# Power_Supply.net
KiCad netlist of a schematic drawn in Altium Designer
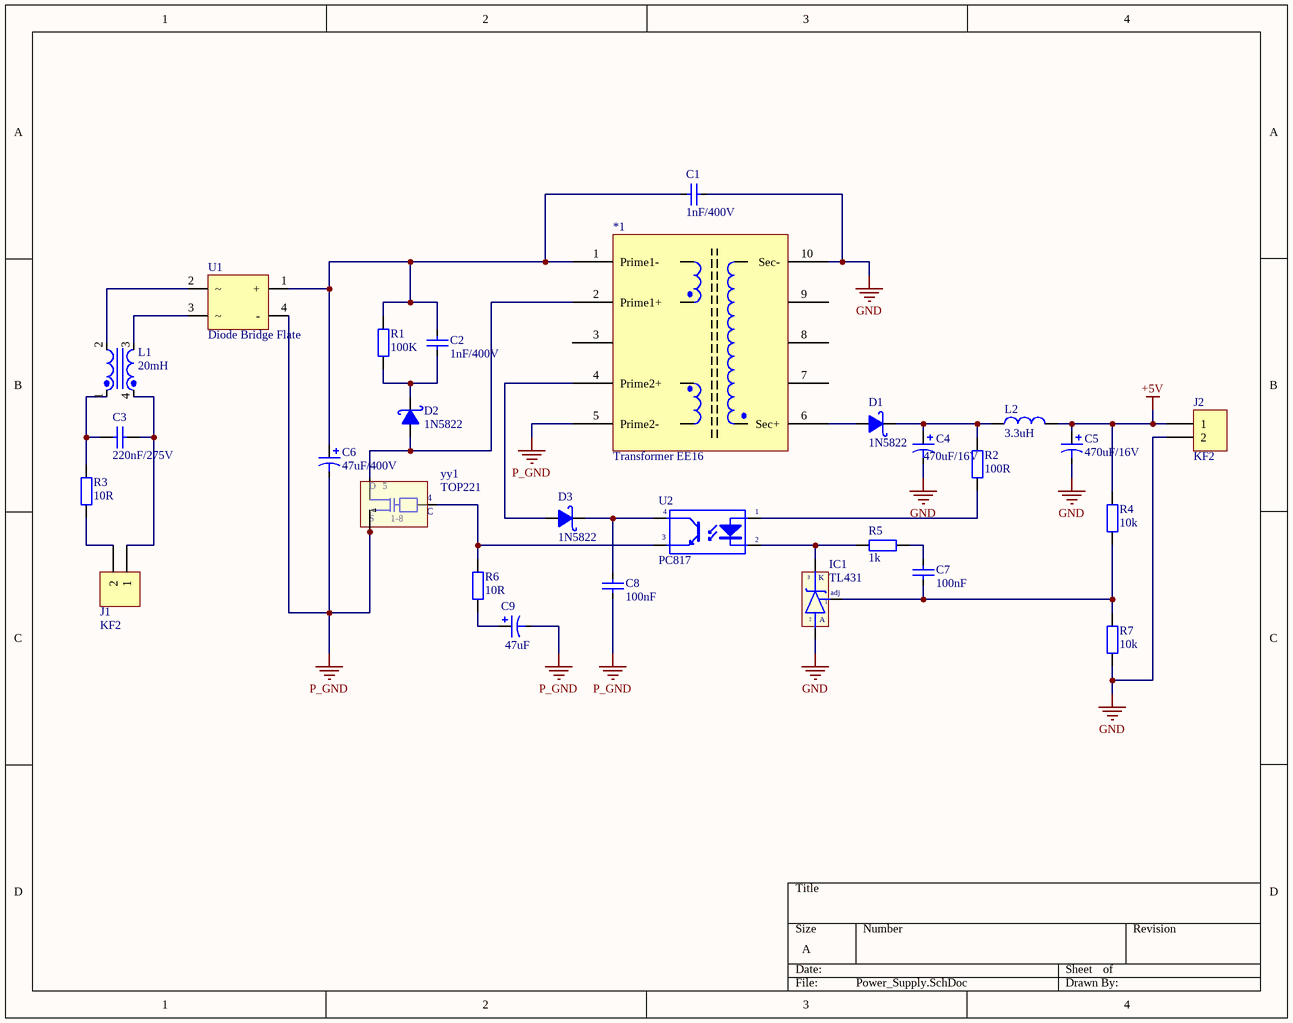
[diagram p0: Power_Supply.SchDoc]

(export (version "E")
  (design (tool "Eeschema 10.0.6"))
  (components
    (comp (ref "*1")
      (value "Transformer EE16")
      (footprint "Transformer SW")
      (libsource (lib "My Library") (part "Transformer EE16"))
    )
    (comp (ref "C1")
      (value "1nF/400V")
      (footprint "103/2KV")
      (description "Capacitor Ceramic 2KV")
      (fields (field (name "PUBLISHER") "Altium Limited"))
      (libsource (lib "My Library") (part "Cap2KV"))
    )
    (comp (ref "C2")
      (value "1nF/400V")
      (footprint "103/2KV")
      (description "Capacitor Ceramic 2KV")
      (fields (field (name "PUBLISHER") "Altium Limited"))
      (libsource (lib "My Library") (part "Cap2KV"))
    )
    (comp (ref "C3")
      (value "220nF/275V")
      (footprint "CN3")
      (description "Capacitor")
      (fields (field (name "Comment") "Capacitor Ceramic") (field (name "PUBLISHER") "Altium Limited"))
      (libsource (lib "My Library") (part "CapCeramic"))
    )
    (comp (ref "C4")
      (value "470uF/16V")
      (footprint "C5mm")
      (description "Polarized Capacitor (Axial)")
      (fields (field (name "PUBLISHER") "Altium Limited"))
      (libsource (lib "My Library") (part "Cap Pol"))
    )
    (comp (ref "C5")
      (value "470uF/16V")
      (footprint "C5mm")
      (description "Polarized Capacitor (Axial)")
      (fields (field (name "PUBLISHER") "Altium Limited"))
      (libsource (lib "My Library") (part "Cap Pol"))
    )
    (comp (ref "C6")
      (value "47uF/400V")
      (footprint "C10mm")
      (description "Polarized Capacitor (Axial)")
      (fields (field (name "PUBLISHER") "Altium Limited"))
      (libsource (lib "My Library") (part "Cap Pol"))
    )
    (comp (ref "C7")
      (value "100nF")
      (footprint "103/2KV")
      (description "Capacitor Ceramic 2KV")
      (fields (field (name "PUBLISHER") "Altium Limited"))
      (libsource (lib "My Library") (part "Cap2KV"))
    )
    (comp (ref "C8")
      (value "100nF")
      (footprint "103/2KV")
      (description "Capacitor Ceramic 2KV")
      (fields (field (name "PUBLISHER") "Altium Limited"))
      (libsource (lib "My Library") (part "Cap2KV"))
    )
    (comp (ref "C9")
      (value "47uF")
      (footprint "C3MM")
      (description "Polarized Capacitor (Axial)")
      (fields (field (name "PUBLISHER") "Altium Limited"))
      (libsource (lib "My Library") (part "Cap Pol"))
    )
    (comp (ref "D1")
      (value "1N5822")
      (footprint "DO-214AC(SMA)")
      (description "Schottky Rectifiers")
      (libsource (lib "My Library") (part "1N5822"))
    )
    (comp (ref "D2")
      (value "1N5822")
      (footprint "DO-214AC(SMA)")
      (description "Schottky Rectifiers")
      (libsource (lib "My Library") (part "1N5822"))
    )
    (comp (ref "D3")
      (value "1N5822")
      (footprint "DO-214AC(SMA)")
      (description "Schottky Rectifiers")
      (libsource (lib "My Library") (part "1N5822"))
    )
    (comp (ref "IC1")
      (value "TL431")
      (footprint "qto-92")
      (description "Programmable Shunt Regulator")
      (libsource (lib "My Library") (part "TL431"))
    )
    (comp (ref "J1")
      (value "KF2")
      (footprint "KF2-5.08")
      (fields
        (field (name "MANUFACTURER") "Würth Elektronik eiSos GmbH")
        (field (name "PARTNO") "691103110002")
        (field (name "CREATED BY") "Karrer Zheng")
      )
      (libsource (lib "") (part "KF2_1"))
    )
    (comp (ref "J2")
      (value "KF2")
      (footprint "KF2-5.08")
      (fields
        (field (name "MANUFACTURER") "Würth Elektronik eiSos GmbH")
        (field (name "PARTNO") "691103110002")
        (field (name "CREATED BY") "Karrer Zheng")
      )
      (libsource (lib "My Library") (part "KF2"))
    )
    (comp (ref "L1")
      (value "20mH")
      (footprint "InductorFilter")
      (description "Inductor")
      (fields (field (name "DESIGNED BY") "VanDungEvn"))
      (libsource (lib "My Library") (part "L fiter"))
    )
    (comp (ref "L2")
      (value "3.3uH")
      (footprint "My Library:L-SMD-M-12x10")
      (description "Inductor")
      (libsource (lib "My Library") (part "Inductor"))
    )
    (comp (ref "R1")
      (value "100K")
      (footprint "RES-1WD")
      (description "Resistor SMD")
      (libsource (lib "My Library") (part "RM"))
    )
    (comp (ref "R2")
      (value "100R")
      (footprint "SM-0805")
      (description "Resistor SMD")
      (libsource (lib "My Library") (part "RM"))
    )
    (comp (ref "R3")
      (value "10R")
      (footprint "RES-1WD")
      (description "Resistor SMD")
      (libsource (lib "My Library") (part "RM"))
    )
    (comp (ref "R4")
      (value "10k")
      (footprint "SM-0805")
      (description "Resistor SMD")
      (libsource (lib "My Library") (part "RM"))
    )
    (comp (ref "R5")
      (value "1k")
      (footprint "SM-0805")
      (description "Resistor SMD")
      (libsource (lib "My Library") (part "RM"))
    )
    (comp (ref "R6")
      (value "10R")
      (footprint "SM-0805")
      (description "Resistor SMD")
      (libsource (lib "My Library") (part "RM"))
    )
    (comp (ref "R7")
      (value "10k")
      (footprint "SM-0805")
      (description "Resistor SMD")
      (libsource (lib "My Library") (part "RM"))
    )
    (comp (ref "U1")
      (value "Diode Bridge Flate")
      (footprint "CAU 1A")
      (description "Diode Bridge")
      (libsource (lib "My Library") (part "Diode Bridge Flate"))
    )
    (comp (ref "U2")
      (value "PC817")
      (footprint "DIP4/W0.3")
      (description "Single Opto")
      (libsource (lib "My Library") (part "PC817"))
    )
    (comp (ref "yy1")
      (value "TOP221")
      (footprint "DIP8/W0.3")
      (description "Family Three-terminal Off-line PWM Switch")
      (libsource (lib "My Library") (part "TOP221-7PG"))
    )
  )
  (nets
    (net (code "1") (name "+5V") (class "Default")
      (node (ref "C5") (pin "1") (pinfunction "1_1") (pintype "passive"))
      (node (ref "J2") (pin "1") (pinfunction "1_1") (pintype "passive"))
      (node (ref "L2") (pin "2") (pinfunction "2_2") (pintype "passive"))
      (node (ref "R4") (pin "1") (pinfunction "1_1") (pintype "passive"))
    )
    (net (code "2") (name "GND") (class "Default")
      (node (ref "*1") (pin "10") (pinfunction "Sec-_10") (pintype "passive"))
      (node (ref "C1") (pin "1") (pinfunction "1_1") (pintype "passive"))
      (node (ref "C4") (pin "2") (pinfunction "2_2") (pintype "passive"))
      (node (ref "C5") (pin "2") (pinfunction "2_2") (pintype "passive"))
      (node (ref "IC1") (pin "2") (pinfunction "A_2") (pintype "passive"))
      (node (ref "J2") (pin "2") (pinfunction "2_2") (pintype "passive"))
      (node (ref "R7") (pin "2") (pinfunction "2_2") (pintype "passive"))
    )
    (net (code "3") (name "Net-(*1-Prime1+)") (class "Default")
      (node (ref "*1") (pin "2") (pinfunction "Prime1+_2") (pintype "passive"))
      (node (ref "D2") (pin "1") (pinfunction "A_1") (pintype "passive"))
      (node (ref "yy1") (pin "5") (pinfunction "D_5") (pintype "passive"))
    )
    (net (code "4") (name "Net-(*1-Prime1-)") (class "Default")
      (node (ref "*1") (pin "1") (pinfunction "Prime1-_1") (pintype "passive"))
      (node (ref "C1") (pin "2") (pinfunction "2_2") (pintype "passive"))
      (node (ref "C2") (pin "2") (pinfunction "2_2") (pintype "passive"))
      (node (ref "C6") (pin "1") (pinfunction "1_1") (pintype "passive"))
      (node (ref "R1") (pin "2") (pinfunction "2_2") (pintype "passive"))
      (node (ref "U1") (pin "1") (pinfunction "+_1") (pintype "passive"))
    )
    (net (code "5") (name "Net-(*1-Prime2+)") (class "Default")
      (node (ref "*1") (pin "4") (pinfunction "Prime2+_4") (pintype "passive"))
      (node (ref "D3") (pin "1") (pinfunction "A_1") (pintype "passive"))
    )
    (net (code "6") (name "Net-(*1-Sec+)") (class "Default")
      (node (ref "*1") (pin "6") (pinfunction "Sec+_6") (pintype "passive"))
      (node (ref "D1") (pin "1") (pinfunction "A_1") (pintype "passive"))
    )
    (net (code "7") (name "Net-(C3-Pad1)") (class "Default")
      (node (ref "C3") (pin "1") (pinfunction "1_1") (pintype "passive"))
      (node (ref "L1") (pin "1") (pintype "passive"))
      (node (ref "R3") (pin "2") (pinfunction "2_2") (pintype "passive"))
    )
    (net (code "8") (name "Net-(C3-Pad2)") (class "Default")
      (node (ref "C3") (pin "2") (pinfunction "2_2") (pintype "passive"))
      (node (ref "J1") (pin "1") (pinfunction "1_1") (pintype "passive"))
      (node (ref "L1") (pin "4") (pintype "passive"))
    )
    (net (code "9") (name "Net-(C7-Pad2)") (class "Default")
      (node (ref "C7") (pin "2") (pinfunction "2_2") (pintype "passive"))
      (node (ref "R5") (pin "1") (pinfunction "1_1") (pintype "passive"))
    )
    (net (code "10") (name "Net-(C9-Pad1)") (class "Default")
      (node (ref "C9") (pin "1") (pinfunction "1_1") (pintype "passive"))
      (node (ref "R6") (pin "1") (pinfunction "1_1") (pintype "passive"))
    )
    (net (code "11") (name "Net-(D1-K)") (class "Default")
      (node (ref "C4") (pin "1") (pinfunction "1_1") (pintype "passive"))
      (node (ref "D1") (pin "2") (pinfunction "K_2") (pintype "passive"))
      (node (ref "L2") (pin "1") (pinfunction "1_1") (pintype "passive"))
      (node (ref "R2") (pin "2") (pinfunction "2_2") (pintype "passive"))
    )
    (net (code "12") (name "Net-(D2-K)") (class "Default")
      (node (ref "C2") (pin "1") (pinfunction "1_1") (pintype "passive"))
      (node (ref "D2") (pin "2") (pinfunction "K_2") (pintype "passive"))
      (node (ref "R1") (pin "1") (pinfunction "1_1") (pintype "passive"))
    )
    (net (code "13") (name "Net-(D3-K)") (class "Default")
      (node (ref "C8") (pin "2") (pinfunction "2_2") (pintype "passive"))
      (node (ref "D3") (pin "2") (pinfunction "K_2") (pintype "passive"))
      (node (ref "U2") (pin "4") (pinfunction "C_4") (pintype "passive"))
    )
    (net (code "14") (name "Net-(IC1-K)") (class "Default")
      (node (ref "IC1") (pin "3") (pinfunction "K_3") (pintype "passive"))
      (node (ref "R5") (pin "2") (pinfunction "2_2") (pintype "passive"))
      (node (ref "U2") (pin "2") (pinfunction "K_2") (pintype "passive"))
    )
    (net (code "15") (name "Net-(IC1-adj)") (class "Default")
      (node (ref "C7") (pin "1") (pinfunction "1_1") (pintype "passive"))
      (node (ref "IC1") (pin "1") (pinfunction "adj_1") (pintype "passive"))
      (node (ref "R4") (pin "2") (pinfunction "2_2") (pintype "passive"))
      (node (ref "R7") (pin "1") (pinfunction "1_1") (pintype "passive"))
    )
    (net (code "16") (name "Net-(J1-Pad2)") (class "Default")
      (node (ref "J1") (pin "2") (pinfunction "2_2") (pintype "passive"))
      (node (ref "R3") (pin "1") (pinfunction "1_1") (pintype "passive"))
    )
    (net (code "17") (name "Net-(L1-Pad2)") (class "Default")
      (node (ref "L1") (pin "2") (pintype "passive"))
      (node (ref "U1") (pin "2") (pinfunction "~_2") (pintype "passive"))
    )
    (net (code "18") (name "Net-(L1-Pad3)") (class "Default")
      (node (ref "L1") (pin "3") (pintype "passive"))
      (node (ref "U1") (pin "3") (pinfunction "~_3") (pintype "passive"))
    )
    (net (code "19") (name "Net-(U2-A)") (class "Default")
      (node (ref "R2") (pin "1") (pinfunction "1_1") (pintype "passive"))
      (node (ref "U2") (pin "1") (pinfunction "A_1") (pintype "passive"))
    )
    (net (code "20") (name "Net-(U2-E)") (class "Default")
      (node (ref "R6") (pin "2") (pinfunction "2_2") (pintype "passive"))
      (node (ref "U2") (pin "3") (pinfunction "E_3") (pintype "passive"))
      (node (ref "yy1") (pin "4") (pinfunction "C_4") (pintype "passive"))
    )
    (net (code "21") (name "P_GND") (class "Default")
      (node (ref "*1") (pin "5") (pinfunction "Prime2-_5") (pintype "passive"))
      (node (ref "C6") (pin "2") (pinfunction "2_2") (pintype "passive"))
      (node (ref "C8") (pin "1") (pinfunction "1_1") (pintype "passive"))
      (node (ref "C9") (pin "2") (pinfunction "2_2") (pintype "passive"))
      (node (ref "U1") (pin "4") (pinfunction "-_4") (pintype "passive"))
      (node (ref "yy1") (pin "1") (pinfunction "S_1") (pintype "passive"))
      (node (ref "yy1") (pin "2") (pinfunction "S_2") (pintype "passive"))
      (node (ref "yy1") (pin "3") (pinfunction "S_3") (pintype "passive"))
      (node (ref "yy1") (pin "6") (pinfunction "S_6") (pintype "passive"))
      (node (ref "yy1") (pin "7") (pinfunction "S_7") (pintype "passive"))
      (node (ref "yy1") (pin "8") (pinfunction "S_8") (pintype "passive"))
    )
    (net (code "22") (name "unconnected-(*1-Pad3)") (class "Default")
      (node (ref "*1") (pin "3") (pintype "passive"))
    )
    (net (code "23") (name "unconnected-(*1-Pad7)") (class "Default")
      (node (ref "*1") (pin "7") (pintype "passive"))
    )
    (net (code "24") (name "unconnected-(*1-Pad8)") (class "Default")
      (node (ref "*1") (pin "8") (pintype "passive"))
    )
    (net (code "25") (name "unconnected-(*1-Pad9)") (class "Default")
      (node (ref "*1") (pin "9") (pintype "passive"))
    )
  )
)
